# AD9959_OUTPUT.net
KiCad netlist of a schematic drawn in Altium Designer
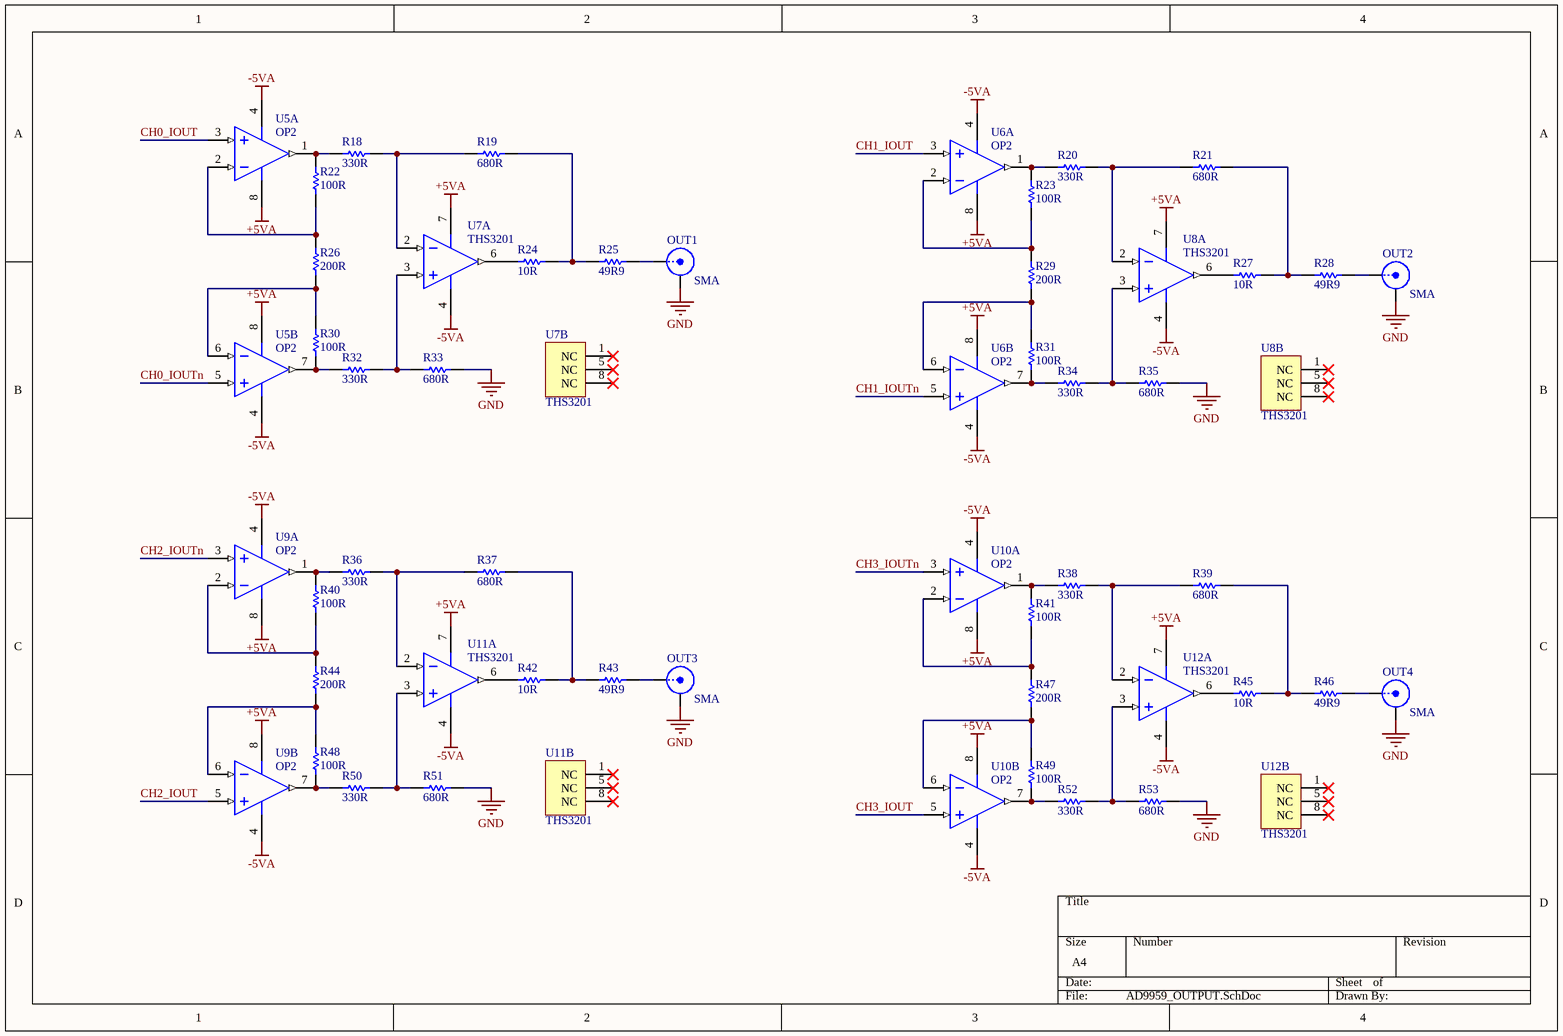
[diagram p0: AD9959_OUTPUT.SchDoc]

(export (version "E")
  (design (tool "Eeschema 10.0.6"))
  (components
    (comp (ref "OUT1")
      (value "SMA")
      (footprint "SMA-V")
      (fields (field (name "PUBLISHER") "Altium Limited"))
      (libsource (lib "Slivy's Library") (part "SMA"))
    )
    (comp (ref "OUT2")
      (value "SMA")
      (footprint "SMA-V")
      (fields (field (name "PUBLISHER") "Altium Limited"))
      (libsource (lib "Slivy's Library") (part "SMA"))
    )
    (comp (ref "OUT3")
      (value "SMA")
      (footprint "SMA-V")
      (fields (field (name "PUBLISHER") "Altium Limited"))
      (libsource (lib "Slivy's Library") (part "SMA"))
    )
    (comp (ref "OUT4")
      (value "SMA")
      (footprint "SMA-V")
      (fields (field (name "PUBLISHER") "Altium Limited"))
      (libsource (lib "Slivy's Library") (part "SMA"))
    )
    (comp (ref "R18")
      (value "330R")
      (footprint "RESC0603(1608)_M")
      (libsource (lib "Slivy's Library") (part "RES"))
    )
    (comp (ref "R19")
      (value "680R")
      (footprint "RESC0603(1608)_M")
      (libsource (lib "Slivy's Library") (part "RES"))
    )
    (comp (ref "R20")
      (value "330R")
      (footprint "RESC0603(1608)_M")
      (libsource (lib "Slivy's Library") (part "RES"))
    )
    (comp (ref "R21")
      (value "680R")
      (footprint "RESC0603(1608)_M")
      (libsource (lib "Slivy's Library") (part "RES"))
    )
    (comp (ref "R22")
      (value "100R")
      (footprint "RESC0603(1608)_M")
      (libsource (lib "Slivy's Library") (part "RES"))
    )
    (comp (ref "R23")
      (value "100R")
      (footprint "RESC0603(1608)_M")
      (libsource (lib "Slivy's Library") (part "RES"))
    )
    (comp (ref "R24")
      (value "10R")
      (footprint "RESC0603(1608)_M")
      (libsource (lib "Slivy's Library") (part "RES"))
    )
    (comp (ref "R25")
      (value "49R9")
      (footprint "RESC0603(1608)_M")
      (libsource (lib "Slivy's Library") (part "RES"))
    )
    (comp (ref "R26")
      (value "200R")
      (footprint "RESC0603(1608)_M")
      (libsource (lib "Slivy's Library") (part "RES"))
    )
    (comp (ref "R27")
      (value "10R")
      (footprint "RESC0603(1608)_M")
      (libsource (lib "Slivy's Library") (part "RES"))
    )
    (comp (ref "R28")
      (value "49R9")
      (footprint "RESC0603(1608)_M")
      (libsource (lib "Slivy's Library") (part "RES"))
    )
    (comp (ref "R29")
      (value "200R")
      (footprint "RESC0603(1608)_M")
      (libsource (lib "Slivy's Library") (part "RES"))
    )
    (comp (ref "R30")
      (value "100R")
      (footprint "RESC0603(1608)_M")
      (libsource (lib "Slivy's Library") (part "RES"))
    )
    (comp (ref "R31")
      (value "100R")
      (footprint "RESC0603(1608)_M")
      (libsource (lib "Slivy's Library") (part "RES"))
    )
    (comp (ref "R32")
      (value "330R")
      (footprint "RESC0603(1608)_M")
      (libsource (lib "Slivy's Library") (part "RES"))
    )
    (comp (ref "R33")
      (value "680R")
      (footprint "RESC0603(1608)_M")
      (libsource (lib "Slivy's Library") (part "RES"))
    )
    (comp (ref "R34")
      (value "330R")
      (footprint "RESC0603(1608)_M")
      (libsource (lib "Slivy's Library") (part "RES"))
    )
    (comp (ref "R35")
      (value "680R")
      (footprint "RESC0603(1608)_M")
      (libsource (lib "Slivy's Library") (part "RES"))
    )
    (comp (ref "R36")
      (value "330R")
      (footprint "RESC0603(1608)_M")
      (libsource (lib "Slivy's Library") (part "RES"))
    )
    (comp (ref "R37")
      (value "680R")
      (footprint "RESC0603(1608)_M")
      (libsource (lib "Slivy's Library") (part "RES"))
    )
    (comp (ref "R38")
      (value "330R")
      (footprint "RESC0603(1608)_M")
      (libsource (lib "Slivy's Library") (part "RES"))
    )
    (comp (ref "R39")
      (value "680R")
      (footprint "RESC0603(1608)_M")
      (libsource (lib "Slivy's Library") (part "RES"))
    )
    (comp (ref "R40")
      (value "100R")
      (footprint "RESC0603(1608)_M")
      (libsource (lib "Slivy's Library") (part "RES"))
    )
    (comp (ref "R41")
      (value "100R")
      (footprint "RESC0603(1608)_M")
      (libsource (lib "Slivy's Library") (part "RES"))
    )
    (comp (ref "R42")
      (value "10R")
      (footprint "RESC0603(1608)_M")
      (libsource (lib "Slivy's Library") (part "RES"))
    )
    (comp (ref "R43")
      (value "49R9")
      (footprint "RESC0603(1608)_M")
      (libsource (lib "Slivy's Library") (part "RES"))
    )
    (comp (ref "R44")
      (value "200R")
      (footprint "RESC0603(1608)_M")
      (libsource (lib "Slivy's Library") (part "RES"))
    )
    (comp (ref "R45")
      (value "10R")
      (footprint "RESC0603(1608)_M")
      (libsource (lib "Slivy's Library") (part "RES"))
    )
    (comp (ref "R46")
      (value "49R9")
      (footprint "RESC0603(1608)_M")
      (libsource (lib "Slivy's Library") (part "RES"))
    )
    (comp (ref "R47")
      (value "200R")
      (footprint "RESC0603(1608)_M")
      (libsource (lib "Slivy's Library") (part "RES"))
    )
    (comp (ref "R48")
      (value "100R")
      (footprint "RESC0603(1608)_M")
      (libsource (lib "Slivy's Library") (part "RES"))
    )
    (comp (ref "R49")
      (value "100R")
      (footprint "RESC0603(1608)_M")
      (libsource (lib "Slivy's Library") (part "RES"))
    )
    (comp (ref "R50")
      (value "330R")
      (footprint "RESC0603(1608)_M")
      (libsource (lib "Slivy's Library") (part "RES"))
    )
    (comp (ref "R51")
      (value "680R")
      (footprint "RESC0603(1608)_M")
      (libsource (lib "Slivy's Library") (part "RES"))
    )
    (comp (ref "R52")
      (value "330R")
      (footprint "RESC0603(1608)_M")
      (libsource (lib "Slivy's Library") (part "RES"))
    )
    (comp (ref "R53")
      (value "680R")
      (footprint "RESC0603(1608)_M")
      (libsource (lib "Slivy's Library") (part "RES"))
    )
    (comp (ref "U5") (value "OP2") (footprint "SOIC8") (libsource (lib "Slivy's Library") (part "OP2")))
    (comp (ref "U6") (value "OP2") (footprint "SOIC8") (libsource (lib "Slivy's Library") (part "OP2")))
    (comp (ref "U7")
      (value "THS3201")
      (footprint "SOIC8")
      (libsource (lib "Slivy's Library") (part "THS3201"))
    )
    (comp (ref "U8")
      (value "THS3201")
      (footprint "SOIC8")
      (libsource (lib "Slivy's Library") (part "THS3201"))
    )
    (comp (ref "U9") (value "OP2") (footprint "SOIC8") (libsource (lib "Slivy's Library") (part "OP2")))
    (comp (ref "U10") (value "OP2") (footprint "SOIC8") (libsource (lib "Slivy's Library") (part "OP2")))
    (comp (ref "U11")
      (value "THS3201")
      (footprint "SOIC8")
      (libsource (lib "Slivy's Library") (part "THS3201"))
    )
    (comp (ref "U12")
      (value "THS3201")
      (footprint "SOIC8")
      (libsource (lib "Slivy's Library") (part "THS3201"))
    )
  )
  (nets
    (net (code "1") (name "+5VA") (class "Default")
      (node (ref "U10") (pin "8") (pinfunction "V+_8") (pintype "power_in"))
      (node (ref "U11") (pin "7") (pinfunction "VS+_7") (pintype "power_in"))
      (node (ref "U12") (pin "7") (pinfunction "VS+_7") (pintype "power_in"))
      (node (ref "U5") (pin "8") (pinfunction "V+_8") (pintype "power_in"))
      (node (ref "U6") (pin "8") (pinfunction "V+_8") (pintype "power_in"))
      (node (ref "U7") (pin "7") (pinfunction "VS+_7") (pintype "power_in"))
      (node (ref "U8") (pin "7") (pinfunction "VS+_7") (pintype "power_in"))
      (node (ref "U9") (pin "8") (pinfunction "V+_8") (pintype "power_in"))
    )
    (net (code "2") (name "-5VA") (class "Default")
      (node (ref "U10") (pin "4") (pinfunction "V-_4") (pintype "power_in"))
      (node (ref "U11") (pin "4") (pinfunction "VS-_4") (pintype "power_in"))
      (node (ref "U12") (pin "4") (pinfunction "VS-_4") (pintype "power_in"))
      (node (ref "U5") (pin "4") (pinfunction "V-_4") (pintype "power_in"))
      (node (ref "U6") (pin "4") (pinfunction "V-_4") (pintype "power_in"))
      (node (ref "U7") (pin "4") (pinfunction "VS-_4") (pintype "power_in"))
      (node (ref "U8") (pin "4") (pinfunction "VS-_4") (pintype "power_in"))
      (node (ref "U9") (pin "4") (pinfunction "V-_4") (pintype "power_in"))
    )
    (net (code "3") (name "/CH0_IOUT") (class "Default")
      (node (ref "U5") (pin "3") (pinfunction "IN_A+_3") (pintype "input"))
    )
    (net (code "4") (name "/CH0_IOUTn") (class "Default")
      (node (ref "U5") (pin "5") (pinfunction "IN_B+_5") (pintype "input"))
    )
    (net (code "5") (name "/CH1_IOUT") (class "Default")
      (node (ref "U6") (pin "3") (pinfunction "IN_A+_3") (pintype "input"))
    )
    (net (code "6") (name "/CH1_IOUTn") (class "Default")
      (node (ref "U6") (pin "5") (pinfunction "IN_B+_5") (pintype "input"))
    )
    (net (code "7") (name "/CH2_IOUT") (class "Default")
      (node (ref "U9") (pin "5") (pinfunction "IN_B+_5") (pintype "input"))
    )
    (net (code "8") (name "/CH2_IOUTn") (class "Default")
      (node (ref "U9") (pin "3") (pinfunction "IN_A+_3") (pintype "input"))
    )
    (net (code "9") (name "/CH3_IOUT") (class "Default")
      (node (ref "U10") (pin "5") (pinfunction "IN_B+_5") (pintype "input"))
    )
    (net (code "10") (name "/CH3_IOUTn") (class "Default")
      (node (ref "U10") (pin "3") (pinfunction "IN_A+_3") (pintype "input"))
    )
    (net (code "11") (name "GND") (class "Default")
      (node (ref "OUT1") (pin "2") (pinfunction "Y_2") (pintype "passive"))
      (node (ref "OUT2") (pin "2") (pinfunction "Y_2") (pintype "passive"))
      (node (ref "OUT3") (pin "2") (pinfunction "Y_2") (pintype "passive"))
      (node (ref "OUT4") (pin "2") (pinfunction "Y_2") (pintype "passive"))
      (node (ref "R33") (pin "2") (pinfunction "2_2") (pintype "passive"))
      (node (ref "R35") (pin "2") (pinfunction "2_2") (pintype "passive"))
      (node (ref "R51") (pin "2") (pinfunction "2_2") (pintype "passive"))
      (node (ref "R53") (pin "2") (pinfunction "2_2") (pintype "passive"))
    )
    (net (code "12") (name "Net-(OUT1-X)") (class "Default")
      (node (ref "OUT1") (pin "1") (pinfunction "X_1") (pintype "passive"))
      (node (ref "R25") (pin "2") (pinfunction "2_2") (pintype "passive"))
    )
    (net (code "13") (name "Net-(OUT2-X)") (class "Default")
      (node (ref "OUT2") (pin "1") (pinfunction "X_1") (pintype "passive"))
      (node (ref "R28") (pin "2") (pinfunction "2_2") (pintype "passive"))
    )
    (net (code "14") (name "Net-(OUT3-X)") (class "Default")
      (node (ref "OUT3") (pin "1") (pinfunction "X_1") (pintype "passive"))
      (node (ref "R43") (pin "2") (pinfunction "2_2") (pintype "passive"))
    )
    (net (code "15") (name "Net-(OUT4-X)") (class "Default")
      (node (ref "OUT4") (pin "1") (pinfunction "X_1") (pintype "passive"))
      (node (ref "R46") (pin "2") (pinfunction "2_2") (pintype "passive"))
    )
    (net (code "16") (name "Net-(R19-Pad2)") (class "Default")
      (node (ref "R19") (pin "2") (pinfunction "2_2") (pintype "passive"))
      (node (ref "R24") (pin "2") (pinfunction "2_2") (pintype "passive"))
      (node (ref "R25") (pin "1") (pinfunction "1_1") (pintype "passive"))
    )
    (net (code "17") (name "Net-(R21-Pad2)") (class "Default")
      (node (ref "R21") (pin "2") (pinfunction "2_2") (pintype "passive"))
      (node (ref "R27") (pin "2") (pinfunction "2_2") (pintype "passive"))
      (node (ref "R28") (pin "1") (pinfunction "1_1") (pintype "passive"))
    )
    (net (code "18") (name "Net-(R37-Pad2)") (class "Default")
      (node (ref "R37") (pin "2") (pinfunction "2_2") (pintype "passive"))
      (node (ref "R42") (pin "2") (pinfunction "2_2") (pintype "passive"))
      (node (ref "R43") (pin "1") (pinfunction "1_1") (pintype "passive"))
    )
    (net (code "19") (name "Net-(R39-Pad2)") (class "Default")
      (node (ref "R39") (pin "2") (pinfunction "2_2") (pintype "passive"))
      (node (ref "R45") (pin "2") (pinfunction "2_2") (pintype "passive"))
      (node (ref "R46") (pin "1") (pinfunction "1_1") (pintype "passive"))
    )
    (net (code "20") (name "Net-(U5A-IN_A-)") (class "Default")
      (node (ref "R22") (pin "1") (pinfunction "1_1") (pintype "passive"))
      (node (ref "R26") (pin "2") (pinfunction "2_2") (pintype "passive"))
      (node (ref "U5") (pin "2") (pinfunction "IN_A-_2") (pintype "input"))
    )
    (net (code "21") (name "Net-(U5A-OUT_A)") (class "Default")
      (node (ref "R18") (pin "1") (pinfunction "1_1") (pintype "passive"))
      (node (ref "R22") (pin "2") (pinfunction "2_2") (pintype "passive"))
      (node (ref "U5") (pin "1") (pinfunction "OUT_A_1") (pintype "output"))
    )
    (net (code "22") (name "Net-(U5B-IN_B-)") (class "Default")
      (node (ref "R26") (pin "1") (pinfunction "1_1") (pintype "passive"))
      (node (ref "R30") (pin "2") (pinfunction "2_2") (pintype "passive"))
      (node (ref "U5") (pin "6") (pinfunction "IN_B-_6") (pintype "input"))
    )
    (net (code "23") (name "Net-(U5B-OUT_B)") (class "Default")
      (node (ref "R30") (pin "1") (pinfunction "1_1") (pintype "passive"))
      (node (ref "R32") (pin "1") (pinfunction "1_1") (pintype "passive"))
      (node (ref "U5") (pin "7") (pinfunction "OUT_B_7") (pintype "output"))
    )
    (net (code "24") (name "Net-(U6A-IN_A-)") (class "Default")
      (node (ref "R23") (pin "1") (pinfunction "1_1") (pintype "passive"))
      (node (ref "R29") (pin "2") (pinfunction "2_2") (pintype "passive"))
      (node (ref "U6") (pin "2") (pinfunction "IN_A-_2") (pintype "input"))
    )
    (net (code "25") (name "Net-(U6A-OUT_A)") (class "Default")
      (node (ref "R20") (pin "1") (pinfunction "1_1") (pintype "passive"))
      (node (ref "R23") (pin "2") (pinfunction "2_2") (pintype "passive"))
      (node (ref "U6") (pin "1") (pinfunction "OUT_A_1") (pintype "output"))
    )
    (net (code "26") (name "Net-(U6B-IN_B-)") (class "Default")
      (node (ref "R29") (pin "1") (pinfunction "1_1") (pintype "passive"))
      (node (ref "R31") (pin "2") (pinfunction "2_2") (pintype "passive"))
      (node (ref "U6") (pin "6") (pinfunction "IN_B-_6") (pintype "input"))
    )
    (net (code "27") (name "Net-(U6B-OUT_B)") (class "Default")
      (node (ref "R31") (pin "1") (pinfunction "1_1") (pintype "passive"))
      (node (ref "R34") (pin "1") (pinfunction "1_1") (pintype "passive"))
      (node (ref "U6") (pin "7") (pinfunction "OUT_B_7") (pintype "output"))
    )
    (net (code "28") (name "Net-(U7A-VIN+)") (class "Default")
      (node (ref "R32") (pin "2") (pinfunction "2_2") (pintype "passive"))
      (node (ref "R33") (pin "1") (pinfunction "1_1") (pintype "passive"))
      (node (ref "U7") (pin "3") (pinfunction "VIN+_3") (pintype "input"))
    )
    (net (code "29") (name "Net-(U7A-VIN-)") (class "Default")
      (node (ref "R18") (pin "2") (pinfunction "2_2") (pintype "passive"))
      (node (ref "R19") (pin "1") (pinfunction "1_1") (pintype "passive"))
      (node (ref "U7") (pin "2") (pinfunction "VIN-_2") (pintype "input"))
    )
    (net (code "30") (name "Net-(U7A-VOUT)") (class "Default")
      (node (ref "R24") (pin "1") (pinfunction "1_1") (pintype "passive"))
      (node (ref "U7") (pin "6") (pinfunction "VOUT_6") (pintype "output"))
    )
    (net (code "31") (name "Net-(U8A-VIN+)") (class "Default")
      (node (ref "R34") (pin "2") (pinfunction "2_2") (pintype "passive"))
      (node (ref "R35") (pin "1") (pinfunction "1_1") (pintype "passive"))
      (node (ref "U8") (pin "3") (pinfunction "VIN+_3") (pintype "input"))
    )
    (net (code "32") (name "Net-(U8A-VIN-)") (class "Default")
      (node (ref "R20") (pin "2") (pinfunction "2_2") (pintype "passive"))
      (node (ref "R21") (pin "1") (pinfunction "1_1") (pintype "passive"))
      (node (ref "U8") (pin "2") (pinfunction "VIN-_2") (pintype "input"))
    )
    (net (code "33") (name "Net-(U8A-VOUT)") (class "Default")
      (node (ref "R27") (pin "1") (pinfunction "1_1") (pintype "passive"))
      (node (ref "U8") (pin "6") (pinfunction "VOUT_6") (pintype "output"))
    )
    (net (code "34") (name "Net-(U9A-IN_A-)") (class "Default")
      (node (ref "R40") (pin "1") (pinfunction "1_1") (pintype "passive"))
      (node (ref "R44") (pin "2") (pinfunction "2_2") (pintype "passive"))
      (node (ref "U9") (pin "2") (pinfunction "IN_A-_2") (pintype "input"))
    )
    (net (code "35") (name "Net-(U9A-OUT_A)") (class "Default")
      (node (ref "R36") (pin "1") (pinfunction "1_1") (pintype "passive"))
      (node (ref "R40") (pin "2") (pinfunction "2_2") (pintype "passive"))
      (node (ref "U9") (pin "1") (pinfunction "OUT_A_1") (pintype "output"))
    )
    (net (code "36") (name "Net-(U9B-IN_B-)") (class "Default")
      (node (ref "R44") (pin "1") (pinfunction "1_1") (pintype "passive"))
      (node (ref "R48") (pin "2") (pinfunction "2_2") (pintype "passive"))
      (node (ref "U9") (pin "6") (pinfunction "IN_B-_6") (pintype "input"))
    )
    (net (code "37") (name "Net-(U9B-OUT_B)") (class "Default")
      (node (ref "R48") (pin "1") (pinfunction "1_1") (pintype "passive"))
      (node (ref "R50") (pin "1") (pinfunction "1_1") (pintype "passive"))
      (node (ref "U9") (pin "7") (pinfunction "OUT_B_7") (pintype "output"))
    )
    (net (code "38") (name "Net-(U10A-IN_A-)") (class "Default")
      (node (ref "R41") (pin "1") (pinfunction "1_1") (pintype "passive"))
      (node (ref "R47") (pin "2") (pinfunction "2_2") (pintype "passive"))
      (node (ref "U10") (pin "2") (pinfunction "IN_A-_2") (pintype "input"))
    )
    (net (code "39") (name "Net-(U10A-OUT_A)") (class "Default")
      (node (ref "R38") (pin "1") (pinfunction "1_1") (pintype "passive"))
      (node (ref "R41") (pin "2") (pinfunction "2_2") (pintype "passive"))
      (node (ref "U10") (pin "1") (pinfunction "OUT_A_1") (pintype "output"))
    )
    (net (code "40") (name "Net-(U10B-IN_B-)") (class "Default")
      (node (ref "R47") (pin "1") (pinfunction "1_1") (pintype "passive"))
      (node (ref "R49") (pin "2") (pinfunction "2_2") (pintype "passive"))
      (node (ref "U10") (pin "6") (pinfunction "IN_B-_6") (pintype "input"))
    )
    (net (code "41") (name "Net-(U10B-OUT_B)") (class "Default")
      (node (ref "R49") (pin "1") (pinfunction "1_1") (pintype "passive"))
      (node (ref "R52") (pin "1") (pinfunction "1_1") (pintype "passive"))
      (node (ref "U10") (pin "7") (pinfunction "OUT_B_7") (pintype "output"))
    )
    (net (code "42") (name "Net-(U11A-VIN+)") (class "Default")
      (node (ref "R50") (pin "2") (pinfunction "2_2") (pintype "passive"))
      (node (ref "R51") (pin "1") (pinfunction "1_1") (pintype "passive"))
      (node (ref "U11") (pin "3") (pinfunction "VIN+_3") (pintype "input"))
    )
    (net (code "43") (name "Net-(U11A-VIN-)") (class "Default")
      (node (ref "R36") (pin "2") (pinfunction "2_2") (pintype "passive"))
      (node (ref "R37") (pin "1") (pinfunction "1_1") (pintype "passive"))
      (node (ref "U11") (pin "2") (pinfunction "VIN-_2") (pintype "input"))
    )
    (net (code "44") (name "Net-(U11A-VOUT)") (class "Default")
      (node (ref "R42") (pin "1") (pinfunction "1_1") (pintype "passive"))
      (node (ref "U11") (pin "6") (pinfunction "VOUT_6") (pintype "output"))
    )
    (net (code "45") (name "Net-(U12A-VIN+)") (class "Default")
      (node (ref "R52") (pin "2") (pinfunction "2_2") (pintype "passive"))
      (node (ref "R53") (pin "1") (pinfunction "1_1") (pintype "passive"))
      (node (ref "U12") (pin "3") (pinfunction "VIN+_3") (pintype "input"))
    )
    (net (code "46") (name "Net-(U12A-VIN-)") (class "Default")
      (node (ref "R38") (pin "2") (pinfunction "2_2") (pintype "passive"))
      (node (ref "R39") (pin "1") (pinfunction "1_1") (pintype "passive"))
      (node (ref "U12") (pin "2") (pinfunction "VIN-_2") (pintype "input"))
    )
    (net (code "47") (name "Net-(U12A-VOUT)") (class "Default")
      (node (ref "R45") (pin "1") (pinfunction "1_1") (pintype "passive"))
      (node (ref "U12") (pin "6") (pinfunction "VOUT_6") (pintype "output"))
    )
    (net (code "48") (name "unconnected-(U7B-NC-Pad1)") (class "Default")
      (node (ref "U7") (pin "1") (pinfunction "NC_1") (pintype "passive+no_connect"))
    )
    (net (code "49") (name "unconnected-(U7B-NC-Pad5)") (class "Default")
      (node (ref "U7") (pin "5") (pinfunction "NC_5") (pintype "passive+no_connect"))
    )
    (net (code "50") (name "unconnected-(U7B-NC-Pad8)") (class "Default")
      (node (ref "U7") (pin "8") (pinfunction "NC_8") (pintype "passive+no_connect"))
    )
    (net (code "51") (name "unconnected-(U8B-NC-Pad1)") (class "Default")
      (node (ref "U8") (pin "1") (pinfunction "NC_1") (pintype "passive+no_connect"))
    )
    (net (code "52") (name "unconnected-(U8B-NC-Pad5)") (class "Default")
      (node (ref "U8") (pin "5") (pinfunction "NC_5") (pintype "passive+no_connect"))
    )
    (net (code "53") (name "unconnected-(U8B-NC-Pad8)") (class "Default")
      (node (ref "U8") (pin "8") (pinfunction "NC_8") (pintype "passive+no_connect"))
    )
    (net (code "54") (name "unconnected-(U11B-NC-Pad1)") (class "Default")
      (node (ref "U11") (pin "1") (pinfunction "NC_1") (pintype "passive+no_connect"))
    )
    (net (code "55") (name "unconnected-(U11B-NC-Pad5)") (class "Default")
      (node (ref "U11") (pin "5") (pinfunction "NC_5") (pintype "passive+no_connect"))
    )
    (net (code "56") (name "unconnected-(U11B-NC-Pad8)") (class "Default")
      (node (ref "U11") (pin "8") (pinfunction "NC_8") (pintype "passive+no_connect"))
    )
    (net (code "57") (name "unconnected-(U12B-NC-Pad1)") (class "Default")
      (node (ref "U12") (pin "1") (pinfunction "NC_1") (pintype "passive+no_connect"))
    )
    (net (code "58") (name "unconnected-(U12B-NC-Pad5)") (class "Default")
      (node (ref "U12") (pin "5") (pinfunction "NC_5") (pintype "passive+no_connect"))
    )
    (net (code "59") (name "unconnected-(U12B-NC-Pad8)") (class "Default")
      (node (ref "U12") (pin "8") (pinfunction "NC_8") (pintype "passive+no_connect"))
    )
  )
)
